# Iron_Driver.net
KiCad netlist of a schematic drawn in Altium Designer
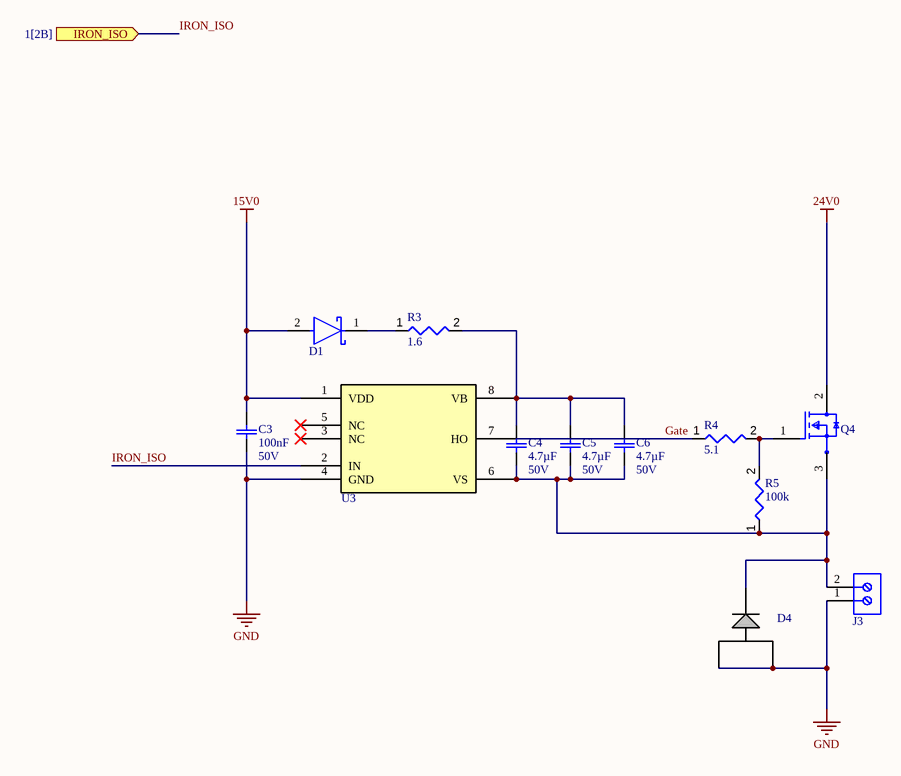
[diagram p0: Iron_Driver.SchDoc]

(export (version "E")
  (design (tool "Eeschema 10.0.6"))
  (components
    (comp (ref "C3")
      (value "100nF")
      (footprint "Generic Ceramic 0603 CAP")
      (fields
        (field (name "VOLTAGE RATING") "50V")
        (field (name "Comment") "CAP-MLCC_SMD-0603_MR-GCM_u_0.1uF_50V_10%_X8L")
      )
      (libsource (lib "Paulo Peixoto") (part "CAP_Ceramic"))
    )
    (comp (ref "C4")
      (value "4.7µF")
      (footprint "Generic Ceramic 0805 CAP")
      (fields
        (field (name "VOLTAGE RATING") "50V")
        (field (name "TOLERANCE") "10%")
        (field (name "Comment") "CAP-MLCC_SMD-0805_TDK-CGA_u_4.7uF_V_10%_X8R")
      )
      (libsource (lib "Paulo Peixoto") (part "CAP_Ceramic"))
    )
    (comp (ref "C5")
      (value "4.7µF")
      (footprint "Generic Ceramic 0805 CAP")
      (fields
        (field (name "VOLTAGE RATING") "50V")
        (field (name "TOLERANCE") "10%")
        (field (name "Comment") "CAP-MLCC_SMD-0805_TDK-CGA_u_4.7uF_V_10%_X8R")
      )
      (libsource (lib "Paulo Peixoto") (part "CAP_Ceramic"))
    )
    (comp (ref "C6")
      (value "4.7µF")
      (footprint "Generic Ceramic 0805 CAP")
      (fields
        (field (name "VOLTAGE RATING") "50V")
        (field (name "TOLERANCE") "10%")
        (field (name "Comment") "CAP-MLCC_SMD-0805_TDK-CGA_u_4.7uF_V_10%_X8R")
      )
      (libsource (lib "Paulo Peixoto") (part "CAP_Ceramic"))
    )
    (comp (ref "D1")
      (value "MBRA340T3G")
      (footprint "ONSC-SMA-2-403D-02_F_V")
      (description "Diode, Schottky Barrier, Vr 40V, If 3A, Pkg SMA, Vf 0.45V, Tj +150degc, Cs 100A, Ir 15mA")
      (libsource (lib "Paulo Peixoto") (part "Generic_Shottky_Diode"))
    )
    (comp (ref "D4")
      (value "STPS1045B")
      (footprint "STPS1045B-Footprint-1")
      (description "Rectifier Diode, Schottky, 1 Phase, 1 Element, 10A, 45V V(RRM), Silicon, TO-252AA")
      (libsource (lib "Paulo Peixoto") (part "STPS1045B-Symbol-1"))
    )
    (comp (ref "J3")
      (value "691137710002")
      (footprint "691137710002")
      (description "2P Block Terminal")
      (libsource (lib "Paulo Peixoto") (part "Generic_2P_Block_Terminal"))
    )
    (comp (ref "Q4")
      (value "STD7NM50N")
      (footprint "STD7NM50N-Footprint-1")
      (description "N-channel 500V - 0.70 Ohm - 5A - TO-220 - TO-220FP - Ipak - Dpak")
      (libsource (lib "Paulo Peixoto") (part "Generic_N_FET"))
    )
    (comp (ref "R3")
      (value "1.6")
      (footprint "Generic_1206_RES")
      (fields
        (field (name "POWER") "750mW")
        (field (name "TOLERANCE") "1%")
        (field (name "Comment") "RES-TK_SMD-1206_VIS-CRCW_R_1.6R_3/4W_1%")
      )
      (libsource (lib "Paulo Peixoto") (part "Res"))
    )
    (comp (ref "R4")
      (value "5.1")
      (footprint "Generic_0805_RES")
      (fields
        (field (name "TOLERANCE") "1%")
        (field (name "POWER") "125mW")
        (field (name "Comment") "RES-TK_SMD-0805_VIS-CRCW_R_5.1R_1/10W_1%")
      )
      (libsource (lib "Paulo Peixoto") (part "Res"))
    )
    (comp (ref "R5")
      (value "100k")
      (footprint "Generic_0805_RES")
      (fields
        (field (name "POWER") "125mW")
        (field (name "TOLERANCE") "1%")
        (field (name "Comment") "RES-TK_SMD-0805_VIS-CRCW_K_100K_1/8W_1%")
      )
      (libsource (lib "Paulo Peixoto") (part "Res"))
    )
    (comp (ref "U3")
      (value "fan73711")
      (footprint "fan73711-Footprint-1")
      (description "Tape & Reel (TR) FAN73711 High-Side 2009 gate driver 25ns 125C 4A 4A 625mW")
      (libsource (lib "Paulo Peixoto") (part "fan73711-Symbol-1"))
    )
  )
  (nets
    (net (code "1") (name "/Gate") (class "Default")
      (node (ref "R4") (pin "1") (pinfunction "1_1") (pintype "passive"))
      (node (ref "U3") (pin "7") (pinfunction "HO_7") (pintype "passive"))
    )
    (net (code "2") (name "/IRON_ISO") (class "Default")
      (node (ref "U3") (pin "2") (pinfunction "IN_2") (pintype "passive"))
    )
    (net (code "3") (name "15V0") (class "Default")
      (node (ref "C3") (pin "2") (pinfunction "2_2") (pintype "passive"))
      (node (ref "D1") (pin "2") (pinfunction "A_2") (pintype "passive"))
      (node (ref "U3") (pin "1") (pinfunction "VDD_1") (pintype "power_in"))
    )
    (net (code "4") (name "24V0") (class "Default")
      (node (ref "Q4") (pin "2") (pinfunction "2_2") (pintype "passive"))
    )
    (net (code "5") (name "GND") (class "Default")
      (node (ref "C3") (pin "1") (pinfunction "1_1") (pintype "passive"))
      (node (ref "D4") (pin "1") (pinfunction "1_1") (pintype "passive"))
      (node (ref "D4") (pin "2") (pinfunction "3_2") (pintype "passive"))
      (node (ref "J3") (pin "1") (pinfunction "1_1") (pintype "passive"))
      (node (ref "U3") (pin "4") (pinfunction "GND_4") (pintype "power_in"))
    )
    (net (code "6") (name "Net-(D1-C)") (class "Default")
      (node (ref "D1") (pin "1") (pinfunction "C_1") (pintype "passive"))
      (node (ref "R3") (pin "1") (pinfunction "1_1") (pintype "passive"))
    )
    (net (code "7") (name "Net-(D4-2)") (class "Default")
      (node (ref "C4") (pin "1") (pinfunction "1_1") (pintype "passive"))
      (node (ref "C5") (pin "1") (pinfunction "1_1") (pintype "passive"))
      (node (ref "C6") (pin "1") (pinfunction "1_1") (pintype "passive"))
      (node (ref "D4") (pin "3") (pinfunction "2_3") (pintype "passive"))
      (node (ref "J3") (pin "2") (pinfunction "2_2") (pintype "passive"))
      (node (ref "Q4") (pin "3") (pinfunction "3_3") (pintype "passive"))
      (node (ref "R5") (pin "1") (pinfunction "1_1") (pintype "passive"))
      (node (ref "U3") (pin "6") (pinfunction "VS_6") (pintype "passive"))
    )
    (net (code "8") (name "Net-(Q4-Pad1)") (class "Default")
      (node (ref "Q4") (pin "1") (pinfunction "1_1") (pintype "passive"))
      (node (ref "R4") (pin "2") (pinfunction "2_2") (pintype "passive"))
      (node (ref "R5") (pin "2") (pinfunction "2_2") (pintype "passive"))
    )
    (net (code "9") (name "Net-(U3-VB)") (class "Default")
      (node (ref "C4") (pin "2") (pinfunction "2_2") (pintype "passive"))
      (node (ref "C5") (pin "2") (pinfunction "2_2") (pintype "passive"))
      (node (ref "C6") (pin "2") (pinfunction "2_2") (pintype "passive"))
      (node (ref "R3") (pin "2") (pinfunction "2_2") (pintype "passive"))
      (node (ref "U3") (pin "8") (pinfunction "VB_8") (pintype "passive"))
    )
    (net (code "10") (name "unconnected-(U3-NC-Pad3)") (class "Default")
      (node (ref "U3") (pin "3") (pinfunction "NC_3") (pintype "passive+no_connect"))
    )
    (net (code "11") (name "unconnected-(U3-NC-Pad5)") (class "Default")
      (node (ref "U3") (pin "5") (pinfunction "NC_5") (pintype "passive+no_connect"))
    )
  )
)
